# Connectors_GPIOs.net
KiCad netlist of a schematic drawn in Altium Designer
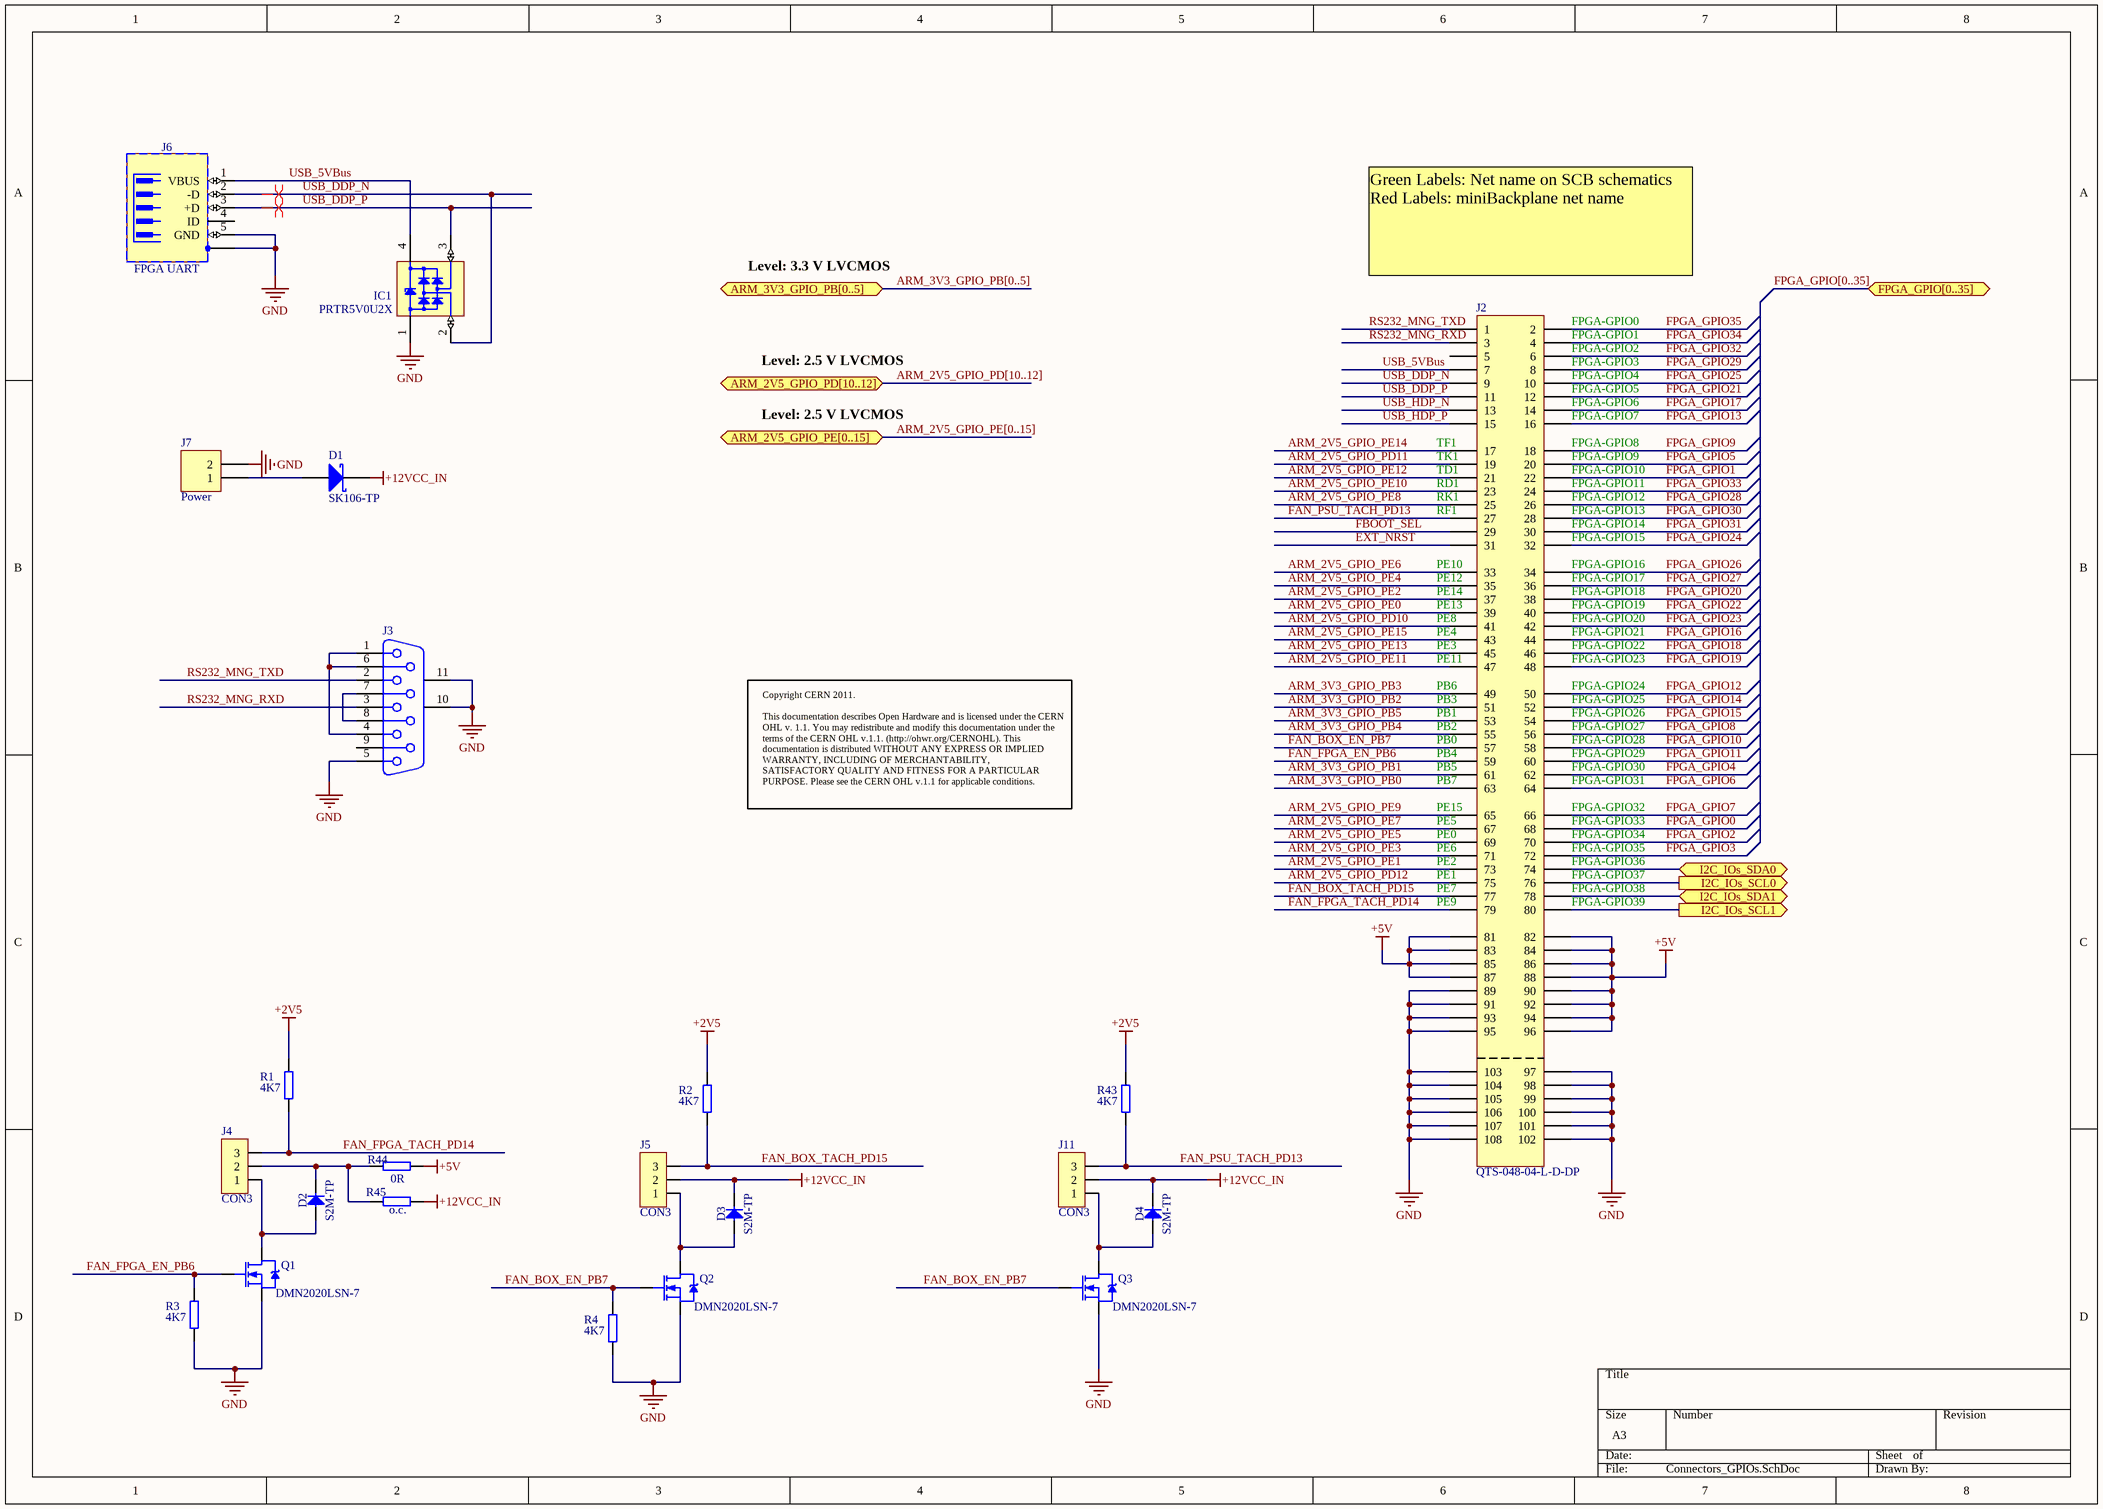
[diagram p0: Connectors_GPIOs.SchDoc]

(export (version "E")
  (design (tool "Eeschema 10.0.6"))
  (components
    (comp (ref "D1")
      (value "SK106-TP")
      (footprint "7S_WR:DO-214AB/SMB-MCC")
      (description "Schottky Diode 10A 60V")
      (libsource (lib "wr_switch") (part "SK106-TP"))
    )
    (comp (ref "D2")
      (value "S2M-TP")
      (footprint "DO-214AA/SMB-MCC")
      (description "2 A Silicon Rectifier 50 to 1000 Volts")
      (fields (field (name "AUTHOR") "CERN DEM JLC"))
      (libsource (lib "wr_switch") (part "S2M-TP"))
    )
    (comp (ref "D3")
      (value "S2M-TP")
      (footprint "DO-214AA/SMB-MCC")
      (description "2 A Silicon Rectifier 50 to 1000 Volts")
      (fields (field (name "AUTHOR") "CERN DEM JLC"))
      (libsource (lib "wr_switch") (part "S2M-TP"))
    )
    (comp (ref "D4")
      (value "S2M-TP")
      (footprint "DO-214AA/SMB-MCC")
      (description "2 A Silicon Rectifier 50 to 1000 Volts")
      (fields (field (name "AUTHOR") "CERN DEM JLC"))
      (libsource (lib "wr_switch") (part "S2M-TP"))
    )
    (comp (ref "IC1")
      (value "PRTR5V0U2X")
      (footprint "7S_WR:SOT190P230X110-4N")
      (description "Ultra Low Capacitance Double Rail-to-Rail ESD Protection Diode")
      (fields
        (field (name "VOLTAGE") "5.5V")
        (field (name "MANUFACTURER") "PHILIPS NXP")
        (field (name "AUTHOR") "CERN DEM JLC")
      )
      (libsource (lib "wr_switch") (part "PRTR5V0U2X"))
    )
    (comp (ref "J2")
      (value "QTS-048-04-L-D-DP")
      (footprint "QTS-048-XX-X-D-DP-A")
      (description "High Speed Ground Plane Header")
      (libsource (lib "wr_switch") (part "QTS-048-01-L-D-DP"))
    )
    (comp (ref "J3")
      (value "D Connector 9")
      (footprint "7S_WR:DSUB1.385-2H9")
      (description "Receptacle Assembly, 9 Position, Right Angle")
      (fields (field (name "PUBLISHER") "Altium Limited"))
      (libsource (lib "Miscellaneous Connectors") (part "D Connector 9"))
    )
    (comp (ref "J4")
      (value "CON3")
      (footprint "7S_WR:MOLEX_22-11-2032")
      (description "Connector")
      (libsource (lib "LIBRARY_SCH") (part "CON3"))
    )
    (comp (ref "J5")
      (value "CON3")
      (footprint "7S_WR:MOLEX_22-11-2032")
      (description "Connector")
      (libsource (lib "LIBRARY_SCH") (part "CON3"))
    )
    (comp (ref "J6")
      (value "FPGA UART")
      (footprint "7S_WR:TYCO_1734035-1")
      (description "5 Pin + 1 Shield USB Receptacle")
      (fields
        (field (name "PART NUMBER") "TYCO_1734035-1")
        (field (name "MANUFACTURER") "TYCO ELECTRONICS")
        (field (name "AUTHOR") "CERN DEM JLC")
      )
      (libsource (lib "Connectors") (part "Connector USB 5 Pin + 1Shield"))
    )
    (comp (ref "J7")
      (value "Power")
      (footprint "7S_WR:TYCO_794120_1")
      (description "Header, 2-Pin")
      (fields (field (name "PUBLISHER") "Altium Limited"))
      (libsource (lib "Miscellaneous Connectors") (part "Header 2"))
    )
    (comp (ref "J11")
      (value "CON3")
      (footprint "7S_WR:MOLEX_22-11-2032")
      (description "Connector")
      (libsource (lib "LIBRARY_SCH") (part "CON3"))
    )
    (comp (ref "Q1")
      (value "DMN2020LSN-7")
      (footprint "7S_WR:SC-59-3")
      (description "N-Channel Power MOSFET")
      (fields (field (name "MANUFACTURER") "Diodes Inc.") (field (name "PUBLISHER") "Altium Limited"))
      (libsource (lib "wr_switch") (part "NMOS-2"))
    )
    (comp (ref "Q2")
      (value "DMN2020LSN-7")
      (footprint "7S_WR:SC-59-3")
      (description "N-Channel Power MOSFET")
      (fields (field (name "MANUFACTURER") "Diodes Inc.") (field (name "PUBLISHER") "Altium Limited"))
      (libsource (lib "wr_switch") (part "NMOS-2"))
    )
    (comp (ref "Q3")
      (value "DMN2020LSN-7")
      (footprint "7S_WR:SC-59-3")
      (description "N-Channel Power MOSFET")
      (fields (field (name "MANUFACTURER") "Diodes Inc.") (field (name "PUBLISHER") "Altium Limited"))
      (libsource (lib "wr_switch") (part "NMOS-2"))
    )
    (comp (ref "R1")
      (value "4K7")
      (footprint "0603")
      (description "SMD Resistor")
      (fields (field (name "TOLERANCE") "±1%"))
      (libsource (lib "wr_switch") (part "RES_SMD"))
    )
    (comp (ref "R2")
      (value "4K7")
      (footprint "0603")
      (description "SMD Resistor")
      (fields (field (name "TOLERANCE") "±1%"))
      (libsource (lib "wr_switch") (part "RES_SMD"))
    )
    (comp (ref "R3")
      (value "4K7")
      (footprint "0603")
      (description "SMD Resistor")
      (fields (field (name "TOLERANCE") "±1%"))
      (libsource (lib "wr_switch") (part "RES_SMD"))
    )
    (comp (ref "R4")
      (value "4K7")
      (footprint "0603")
      (description "SMD Resistor")
      (fields (field (name "TOLERANCE") "±1%"))
      (libsource (lib "wr_switch") (part "RES_SMD"))
    )
    (comp (ref "R43")
      (value "4K7")
      (footprint "0603")
      (description "SMD Resistor")
      (fields (field (name "TOLERANCE") "±1%"))
      (libsource (lib "wr_switch") (part "RES_SMD"))
    )
    (comp (ref "R44")
      (value "0R")
      (footprint "0603")
      (description "SMD Resistor")
      (libsource (lib "wr_switch") (part "RES_SMD"))
    )
    (comp (ref "R45")
      (value "o.c.")
      (footprint "0603")
      (description "SMD Resistor")
      (fields (field (name "TOLERANCE") "NA"))
      (libsource (lib "wr_switch") (part "RES_SMD"))
    )
  )
  (nets
    (net (code "1") (name "+2V5") (class "Default")
      (node (ref "R1") (pin "1") (pinfunction "1_1") (pintype "passive"))
      (node (ref "R2") (pin "1") (pinfunction "1_1") (pintype "passive"))
      (node (ref "R43") (pin "1") (pinfunction "1_1") (pintype "passive"))
    )
    (net (code "2") (name "+5V") (class "Default")
      (node (ref "J2") (pin "81") (pinfunction "81_81") (pintype "passive"))
      (node (ref "J2") (pin "82") (pinfunction "82_82") (pintype "passive"))
      (node (ref "J2") (pin "83") (pinfunction "83_83") (pintype "passive"))
      (node (ref "J2") (pin "84") (pinfunction "84_84") (pintype "passive"))
      (node (ref "J2") (pin "85") (pinfunction "85_85") (pintype "passive"))
      (node (ref "J2") (pin "86") (pinfunction "86_86") (pintype "passive"))
      (node (ref "J2") (pin "87") (pinfunction "87_87") (pintype "passive"))
      (node (ref "J2") (pin "88") (pinfunction "88_88") (pintype "passive"))
      (node (ref "J2") (pin "90") (pinfunction "90_90") (pintype "passive"))
      (node (ref "J2") (pin "92") (pinfunction "92_92") (pintype "passive"))
      (node (ref "J2") (pin "94") (pinfunction "94_94") (pintype "passive"))
      (node (ref "J2") (pin "96") (pinfunction "96_96") (pintype "passive"))
      (node (ref "R44") (pin "2") (pinfunction "2_2") (pintype "passive"))
    )
    (net (code "3") (name "+12VCC_IN") (class "Default")
      (node (ref "D1") (pin "1") (pinfunction "K_1") (pintype "passive"))
      (node (ref "D3") (pin "1") (pinfunction "C_1") (pintype "passive"))
      (node (ref "D4") (pin "1") (pinfunction "C_1") (pintype "passive"))
      (node (ref "J11") (pin "2") (pinfunction "2_2") (pintype "passive"))
      (node (ref "J5") (pin "2") (pinfunction "2_2") (pintype "passive"))
      (node (ref "R45") (pin "1") (pinfunction "1_1") (pintype "passive"))
    )
    (net (code "4") (name "/ARM_2V5_GPIO_PD10") (class "Default")
      (node (ref "J2") (pin "41") (pinfunction "41_41") (pintype "passive"))
    )
    (net (code "5") (name "/ARM_2V5_GPIO_PD11") (class "Default")
      (node (ref "J2") (pin "19") (pinfunction "19_19") (pintype "passive"))
    )
    (net (code "6") (name "/ARM_2V5_GPIO_PD12") (class "Default")
      (node (ref "J2") (pin "75") (pinfunction "75_75") (pintype "passive"))
    )
    (net (code "8") (name "/ARM_2V5_GPIO_PE0") (class "Default")
      (node (ref "J2") (pin "39") (pinfunction "39_39") (pintype "passive"))
    )
    (net (code "9") (name "/ARM_2V5_GPIO_PE1") (class "Default")
      (node (ref "J2") (pin "73") (pinfunction "73_73") (pintype "passive"))
    )
    (net (code "10") (name "/ARM_2V5_GPIO_PE2") (class "Default")
      (node (ref "J2") (pin "37") (pinfunction "37_37") (pintype "passive"))
    )
    (net (code "11") (name "/ARM_2V5_GPIO_PE3") (class "Default")
      (node (ref "J2") (pin "71") (pinfunction "71_71") (pintype "passive"))
    )
    (net (code "12") (name "/ARM_2V5_GPIO_PE4") (class "Default")
      (node (ref "J2") (pin "35") (pinfunction "35_35") (pintype "passive"))
    )
    (net (code "13") (name "/ARM_2V5_GPIO_PE5") (class "Default")
      (node (ref "J2") (pin "69") (pinfunction "69_69") (pintype "passive"))
    )
    (net (code "14") (name "/ARM_2V5_GPIO_PE6") (class "Default")
      (node (ref "J2") (pin "33") (pinfunction "33_33") (pintype "passive"))
    )
    (net (code "15") (name "/ARM_2V5_GPIO_PE7") (class "Default")
      (node (ref "J2") (pin "67") (pinfunction "67_67") (pintype "passive"))
    )
    (net (code "16") (name "/ARM_2V5_GPIO_PE8") (class "Default")
      (node (ref "J2") (pin "25") (pinfunction "25_25") (pintype "passive"))
    )
    (net (code "17") (name "/ARM_2V5_GPIO_PE9") (class "Default")
      (node (ref "J2") (pin "65") (pinfunction "65_65") (pintype "passive"))
    )
    (net (code "18") (name "/ARM_2V5_GPIO_PE10") (class "Default")
      (node (ref "J2") (pin "23") (pinfunction "23_23") (pintype "passive"))
    )
    (net (code "19") (name "/ARM_2V5_GPIO_PE11") (class "Default")
      (node (ref "J2") (pin "47") (pinfunction "47_47") (pintype "passive"))
    )
    (net (code "20") (name "/ARM_2V5_GPIO_PE12") (class "Default")
      (node (ref "J2") (pin "21") (pinfunction "21_21") (pintype "passive"))
    )
    (net (code "21") (name "/ARM_2V5_GPIO_PE13") (class "Default")
      (node (ref "J2") (pin "45") (pinfunction "45_45") (pintype "passive"))
    )
    (net (code "22") (name "/ARM_2V5_GPIO_PE14") (class "Default")
      (node (ref "J2") (pin "17") (pinfunction "17_17") (pintype "passive"))
    )
    (net (code "23") (name "/ARM_2V5_GPIO_PE15") (class "Default")
      (node (ref "J2") (pin "43") (pinfunction "43_43") (pintype "passive"))
    )
    (net (code "25") (name "/ARM_3V3_GPIO_PB0") (class "Default")
      (node (ref "J2") (pin "63") (pinfunction "63_63") (pintype "passive"))
    )
    (net (code "26") (name "/ARM_3V3_GPIO_PB1") (class "Default")
      (node (ref "J2") (pin "61") (pinfunction "61_61") (pintype "passive"))
    )
    (net (code "27") (name "/ARM_3V3_GPIO_PB2") (class "Default")
      (node (ref "J2") (pin "51") (pinfunction "51_51") (pintype "passive"))
    )
    (net (code "28") (name "/ARM_3V3_GPIO_PB3") (class "Default")
      (node (ref "J2") (pin "49") (pinfunction "49_49") (pintype "passive"))
    )
    (net (code "29") (name "/ARM_3V3_GPIO_PB4") (class "Default")
      (node (ref "J2") (pin "55") (pinfunction "55_55") (pintype "passive"))
    )
    (net (code "30") (name "/ARM_3V3_GPIO_PB5") (class "Default")
      (node (ref "J2") (pin "53") (pinfunction "53_53") (pintype "passive"))
    )
    (net (code "32") (name "/EXT_NRST") (class "Default")
      (node (ref "J2") (pin "31") (pinfunction "31_31") (pintype "passive"))
    )
    (net (code "33") (name "/FAN_BOX_EN_PB7") (class "Default")
      (node (ref "J2") (pin "57") (pinfunction "57_57") (pintype "passive"))
      (node (ref "Q2") (pin "1") (pinfunction "G_1") (pintype "passive"))
      (node (ref "Q3") (pin "1") (pinfunction "G_1") (pintype "passive"))
      (node (ref "R4") (pin "1") (pinfunction "1_1") (pintype "passive"))
    )
    (net (code "34") (name "/FAN_BOX_TACH_PD15") (class "Default")
      (node (ref "J2") (pin "77") (pinfunction "77_77") (pintype "passive"))
      (node (ref "J5") (pin "3") (pinfunction "3_3") (pintype "passive"))
      (node (ref "R2") (pin "2") (pinfunction "2_2") (pintype "passive"))
    )
    (net (code "35") (name "/FAN_FPGA_EN_PB6") (class "Default")
      (node (ref "J2") (pin "59") (pinfunction "59_59") (pintype "passive"))
      (node (ref "Q1") (pin "1") (pinfunction "G_1") (pintype "passive"))
      (node (ref "R3") (pin "1") (pinfunction "1_1") (pintype "passive"))
    )
    (net (code "36") (name "/FAN_FPGA_TACH_PD14") (class "Default")
      (node (ref "J2") (pin "79") (pinfunction "79_79") (pintype "passive"))
      (node (ref "J4") (pin "3") (pinfunction "3_3") (pintype "passive"))
      (node (ref "R1") (pin "2") (pinfunction "2_2") (pintype "passive"))
    )
    (net (code "37") (name "/FAN_PSU_TACH_PD13") (class "Default")
      (node (ref "J11") (pin "3") (pinfunction "3_3") (pintype "passive"))
      (node (ref "J2") (pin "27") (pinfunction "27_27") (pintype "passive"))
      (node (ref "R43") (pin "2") (pinfunction "2_2") (pintype "passive"))
    )
    (net (code "38") (name "/FBOOT_SEL") (class "Default")
      (node (ref "J2") (pin "29") (pinfunction "29_29") (pintype "passive"))
    )
    (net (code "39") (name "/FPGA-GPIO36") (class "Default")
      (node (ref "J2") (pin "74") (pinfunction "74_74") (pintype "passive"))
    )
    (net (code "40") (name "/FPGA-GPIO37") (class "Default")
      (node (ref "J2") (pin "76") (pinfunction "76_76") (pintype "passive"))
    )
    (net (code "41") (name "/FPGA-GPIO38") (class "Default")
      (node (ref "J2") (pin "78") (pinfunction "78_78") (pintype "passive"))
    )
    (net (code "42") (name "/FPGA-GPIO39") (class "Default")
      (node (ref "J2") (pin "80") (pinfunction "80_80") (pintype "passive"))
    )
    (net (code "43") (name "/FPGA_GPIO0") (class "Default")
      (node (ref "J2") (pin "68") (pinfunction "68_68") (pintype "passive"))
    )
    (net (code "44") (name "/FPGA_GPIO1") (class "Default")
      (node (ref "J2") (pin "22") (pinfunction "22_22") (pintype "passive"))
    )
    (net (code "45") (name "/FPGA_GPIO2") (class "Default")
      (node (ref "J2") (pin "70") (pinfunction "70_70") (pintype "passive"))
    )
    (net (code "46") (name "/FPGA_GPIO3") (class "Default")
      (node (ref "J2") (pin "72") (pinfunction "72_72") (pintype "passive"))
    )
    (net (code "47") (name "/FPGA_GPIO4") (class "Default")
      (node (ref "J2") (pin "62") (pinfunction "62_62") (pintype "passive"))
    )
    (net (code "48") (name "/FPGA_GPIO5") (class "Default")
      (node (ref "J2") (pin "20") (pinfunction "20_20") (pintype "passive"))
    )
    (net (code "49") (name "/FPGA_GPIO6") (class "Default")
      (node (ref "J2") (pin "64") (pinfunction "64_64") (pintype "passive"))
    )
    (net (code "50") (name "/FPGA_GPIO7") (class "Default")
      (node (ref "J2") (pin "66") (pinfunction "66_66") (pintype "passive"))
    )
    (net (code "51") (name "/FPGA_GPIO8") (class "Default")
      (node (ref "J2") (pin "56") (pinfunction "56_56") (pintype "passive"))
    )
    (net (code "52") (name "/FPGA_GPIO9") (class "Default")
      (node (ref "J2") (pin "18") (pinfunction "18_18") (pintype "passive"))
    )
    (net (code "53") (name "/FPGA_GPIO10") (class "Default")
      (node (ref "J2") (pin "58") (pinfunction "58_58") (pintype "passive"))
    )
    (net (code "54") (name "/FPGA_GPIO11") (class "Default")
      (node (ref "J2") (pin "60") (pinfunction "60_60") (pintype "passive"))
    )
    (net (code "55") (name "/FPGA_GPIO12") (class "Default")
      (node (ref "J2") (pin "50") (pinfunction "50_50") (pintype "passive"))
    )
    (net (code "56") (name "/FPGA_GPIO13") (class "Default")
      (node (ref "J2") (pin "16") (pinfunction "16_16") (pintype "passive"))
    )
    (net (code "57") (name "/FPGA_GPIO14") (class "Default")
      (node (ref "J2") (pin "52") (pinfunction "52_52") (pintype "passive"))
    )
    (net (code "58") (name "/FPGA_GPIO15") (class "Default")
      (node (ref "J2") (pin "54") (pinfunction "54_54") (pintype "passive"))
    )
    (net (code "59") (name "/FPGA_GPIO16") (class "Default")
      (node (ref "J2") (pin "44") (pinfunction "44_44") (pintype "passive"))
    )
    (net (code "60") (name "/FPGA_GPIO17") (class "Default")
      (node (ref "J2") (pin "14") (pinfunction "14_14") (pintype "passive"))
    )
    (net (code "61") (name "/FPGA_GPIO18") (class "Default")
      (node (ref "J2") (pin "46") (pinfunction "46_46") (pintype "passive"))
    )
    (net (code "62") (name "/FPGA_GPIO19") (class "Default")
      (node (ref "J2") (pin "48") (pinfunction "48_48") (pintype "passive"))
    )
    (net (code "63") (name "/FPGA_GPIO20") (class "Default")
      (node (ref "J2") (pin "38") (pinfunction "38_38") (pintype "passive"))
    )
    (net (code "64") (name "/FPGA_GPIO21") (class "Default")
      (node (ref "J2") (pin "12") (pinfunction "12_12") (pintype "passive"))
    )
    (net (code "65") (name "/FPGA_GPIO22") (class "Default")
      (node (ref "J2") (pin "40") (pinfunction "40_40") (pintype "passive"))
    )
    (net (code "66") (name "/FPGA_GPIO23") (class "Default")
      (node (ref "J2") (pin "42") (pinfunction "42_42") (pintype "passive"))
    )
    (net (code "67") (name "/FPGA_GPIO24") (class "Default")
      (node (ref "J2") (pin "32") (pinfunction "32_32") (pintype "passive"))
    )
    (net (code "68") (name "/FPGA_GPIO25") (class "Default")
      (node (ref "J2") (pin "10") (pinfunction "10_10") (pintype "passive"))
    )
    (net (code "69") (name "/FPGA_GPIO26") (class "Default")
      (node (ref "J2") (pin "34") (pinfunction "34_34") (pintype "passive"))
    )
    (net (code "70") (name "/FPGA_GPIO27") (class "Default")
      (node (ref "J2") (pin "36") (pinfunction "36_36") (pintype "passive"))
    )
    (net (code "71") (name "/FPGA_GPIO28") (class "Default")
      (node (ref "J2") (pin "26") (pinfunction "26_26") (pintype "passive"))
    )
    (net (code "72") (name "/FPGA_GPIO29") (class "Default")
      (node (ref "J2") (pin "8") (pinfunction "8_8") (pintype "passive"))
    )
    (net (code "73") (name "/FPGA_GPIO30") (class "Default")
      (node (ref "J2") (pin "28") (pinfunction "28_28") (pintype "passive"))
    )
    (net (code "74") (name "/FPGA_GPIO31") (class "Default")
      (node (ref "J2") (pin "30") (pinfunction "30_30") (pintype "passive"))
    )
    (net (code "75") (name "/FPGA_GPIO32") (class "Default")
      (node (ref "J2") (pin "6") (pinfunction "6_6") (pintype "passive"))
    )
    (net (code "76") (name "/FPGA_GPIO33") (class "Default")
      (node (ref "J2") (pin "24") (pinfunction "24_24") (pintype "passive"))
    )
    (net (code "77") (name "/FPGA_GPIO34") (class "Default")
      (node (ref "J2") (pin "4") (pinfunction "4_4") (pintype "passive"))
    )
    (net (code "78") (name "/FPGA_GPIO35") (class "Default")
      (node (ref "J2") (pin "2") (pinfunction "2_2") (pintype "passive"))
    )
    (net (code "80") (name "/RS232_MNG_RXD") (class "Default")
      (node (ref "J2") (pin "3") (pinfunction "3_3") (pintype "passive"))
      (node (ref "J3") (pin "3") (pinfunction "3_3") (pintype "passive"))
    )
    (net (code "81") (name "/RS232_MNG_TXD") (class "Default")
      (node (ref "J2") (pin "1") (pinfunction "1_1") (pintype "passive"))
      (node (ref "J3") (pin "2") (pinfunction "2_2") (pintype "passive"))
    )
    (net (code "82") (name "/USB_5VBus") (class "Default")
      (node (ref "IC1") (pin "4") (pinfunction "VCC_4") (pintype "power_in"))
      (node (ref "J2") (pin "7") (pinfunction "7_7") (pintype "passive"))
      (node (ref "J6") (pin "1") (pinfunction "VBUS_1") (pintype "bidirectional"))
    )
    (net (code "83") (name "/USB_DDP_N") (class "Default")
      (node (ref "IC1") (pin "2") (pinfunction "I/O1_2") (pintype "bidirectional"))
      (node (ref "J2") (pin "9") (pinfunction "9_9") (pintype "passive"))
      (node (ref "J6") (pin "2") (pinfunction "-D_2") (pintype "bidirectional"))
    )
    (net (code "84") (name "/USB_DDP_P") (class "Default")
      (node (ref "IC1") (pin "3") (pinfunction "I/O2_3") (pintype "bidirectional"))
      (node (ref "J2") (pin "11") (pinfunction "11_11") (pintype "passive"))
      (node (ref "J6") (pin "3") (pinfunction "+D_3") (pintype "bidirectional"))
    )
    (net (code "85") (name "/USB_HDP_N") (class "Default")
      (node (ref "J2") (pin "13") (pinfunction "13_13") (pintype "passive"))
    )
    (net (code "86") (name "/USB_HDP_P") (class "Default")
      (node (ref "J2") (pin "15") (pinfunction "15_15") (pintype "passive"))
    )
    (net (code "87") (name "GND") (class "Default")
      (node (ref "IC1") (pin "1") (pinfunction "GND_1") (pintype "power_in"))
      (node (ref "J2") (pin "100") (pinfunction "100_100") (pintype "passive"))
      (node (ref "J2") (pin "101") (pinfunction "101_101") (pintype "passive"))
      (node (ref "J2") (pin "102") (pinfunction "102_102") (pintype "passive"))
      (node (ref "J2") (pin "103") (pinfunction "103_103") (pintype "passive"))
      (node (ref "J2") (pin "104") (pinfunction "104_104") (pintype "passive"))
      (node (ref "J2") (pin "105") (pinfunction "105_105") (pintype "passive"))
      (node (ref "J2") (pin "106") (pinfunction "106_106") (pintype "passive"))
      (node (ref "J2") (pin "107") (pinfunction "107_107") (pintype "passive"))
      (node (ref "J2") (pin "108") (pinfunction "108_108") (pintype "passive"))
      (node (ref "J2") (pin "89") (pinfunction "89_89") (pintype "passive"))
      (node (ref "J2") (pin "91") (pinfunction "91_91") (pintype "passive"))
      (node (ref "J2") (pin "93") (pinfunction "93_93") (pintype "passive"))
      (node (ref "J2") (pin "95") (pinfunction "95_95") (pintype "passive"))
      (node (ref "J2") (pin "97") (pinfunction "97_97") (pintype "passive"))
      (node (ref "J2") (pin "98") (pinfunction "98_98") (pintype "passive"))
      (node (ref "J2") (pin "99") (pinfunction "99_99") (pintype "passive"))
      (node (ref "J3") (pin "10") (pinfunction "MH1_10") (pintype "passive"))
      (node (ref "J3") (pin "11") (pinfunction "MH2_11") (pintype "passive"))
      (node (ref "J3") (pin "5") (pinfunction "5_5") (pintype "passive"))
      (node (ref "J6") (pin "5") (pinfunction "GND_5") (pintype "bidirectional"))
      (node (ref "J6") (pin "6") (pinfunction "SH_6") (pintype "power_in"))
      (node (ref "J7") (pin "2") (pinfunction "2_2") (pintype "passive"))
      (node (ref "Q1") (pin "3") (pinfunction "S_3") (pintype "passive"))
      (node (ref "Q2") (pin "3") (pinfunction "S_3") (pintype "passive"))
      (node (ref "Q3") (pin "3") (pinfunction "S_3") (pintype "passive"))
      (node (ref "R3") (pin "2") (pinfunction "2_2") (pintype "passive"))
      (node (ref "R4") (pin "2") (pinfunction "2_2") (pintype "passive"))
    )
    (net (code "88") (name "Net-(D1-A)") (class "Default")
      (node (ref "D1") (pin "2") (pinfunction "A_2") (pintype "passive"))
      (node (ref "J7") (pin "1") (pinfunction "1_1") (pintype "passive"))
    )
    (net (code "89") (name "Net-(D2-A)") (class "Default")
      (node (ref "D2") (pin "2") (pinfunction "A_2") (pintype "passive"))
      (node (ref "J4") (pin "1") (pinfunction "1_1") (pintype "passive"))
      (node (ref "Q1") (pin "2") (pinfunction "D_2") (pintype "passive"))
    )
    (net (code "90") (name "Net-(D2-C)") (class "Default")
      (node (ref "D2") (pin "1") (pinfunction "C_1") (pintype "passive"))
      (node (ref "J4") (pin "2") (pinfunction "2_2") (pintype "passive"))
      (node (ref "R44") (pin "1") (pinfunction "1_1") (pintype "passive"))
      (node (ref "R45") (pin "2") (pinfunction "2_2") (pintype "passive"))
    )
    (net (code "91") (name "Net-(D3-A)") (class "Default")
      (node (ref "D3") (pin "2") (pinfunction "A_2") (pintype "passive"))
      (node (ref "J5") (pin "1") (pinfunction "1_1") (pintype "passive"))
      (node (ref "Q2") (pin "2") (pinfunction "D_2") (pintype "passive"))
    )
    (net (code "92") (name "Net-(D4-A)") (class "Default")
      (node (ref "D4") (pin "2") (pinfunction "A_2") (pintype "passive"))
      (node (ref "J11") (pin "1") (pinfunction "1_1") (pintype "passive"))
      (node (ref "Q3") (pin "2") (pinfunction "D_2") (pintype "passive"))
    )
    (net (code "93") (name "Net-(J3-Pad1)") (class "Default")
      (node (ref "J3") (pin "1") (pinfunction "1_1") (pintype "passive"))
      (node (ref "J3") (pin "4") (pinfunction "4_4") (pintype "passive"))
      (node (ref "J3") (pin "6") (pinfunction "6_6") (pintype "passive"))
    )
    (net (code "94") (name "Net-(J3-Pad7)") (class "Default")
      (node (ref "J3") (pin "7") (pinfunction "7_7") (pintype "passive"))
      (node (ref "J3") (pin "8") (pinfunction "8_8") (pintype "passive"))
    )
    (net (code "95") (name "unconnected-(J2-Pad5)") (class "Default")
      (node (ref "J2") (pin "5") (pinfunction "5_5") (pintype "passive"))
    )
    (net (code "96") (name "unconnected-(J3-Pad9)") (class "Default")
      (node (ref "J3") (pin "9") (pinfunction "9_9") (pintype "passive"))
    )
    (net (code "97") (name "unconnected-(J6-ID-Pad4)") (class "Default")
      (node (ref "J6") (pin "4") (pinfunction "ID_4") (pintype "passive"))
    )
  )
)
